# 07_MIMXRT1170_PART3.net
KiCad netlist of a schematic drawn in Altium Designer
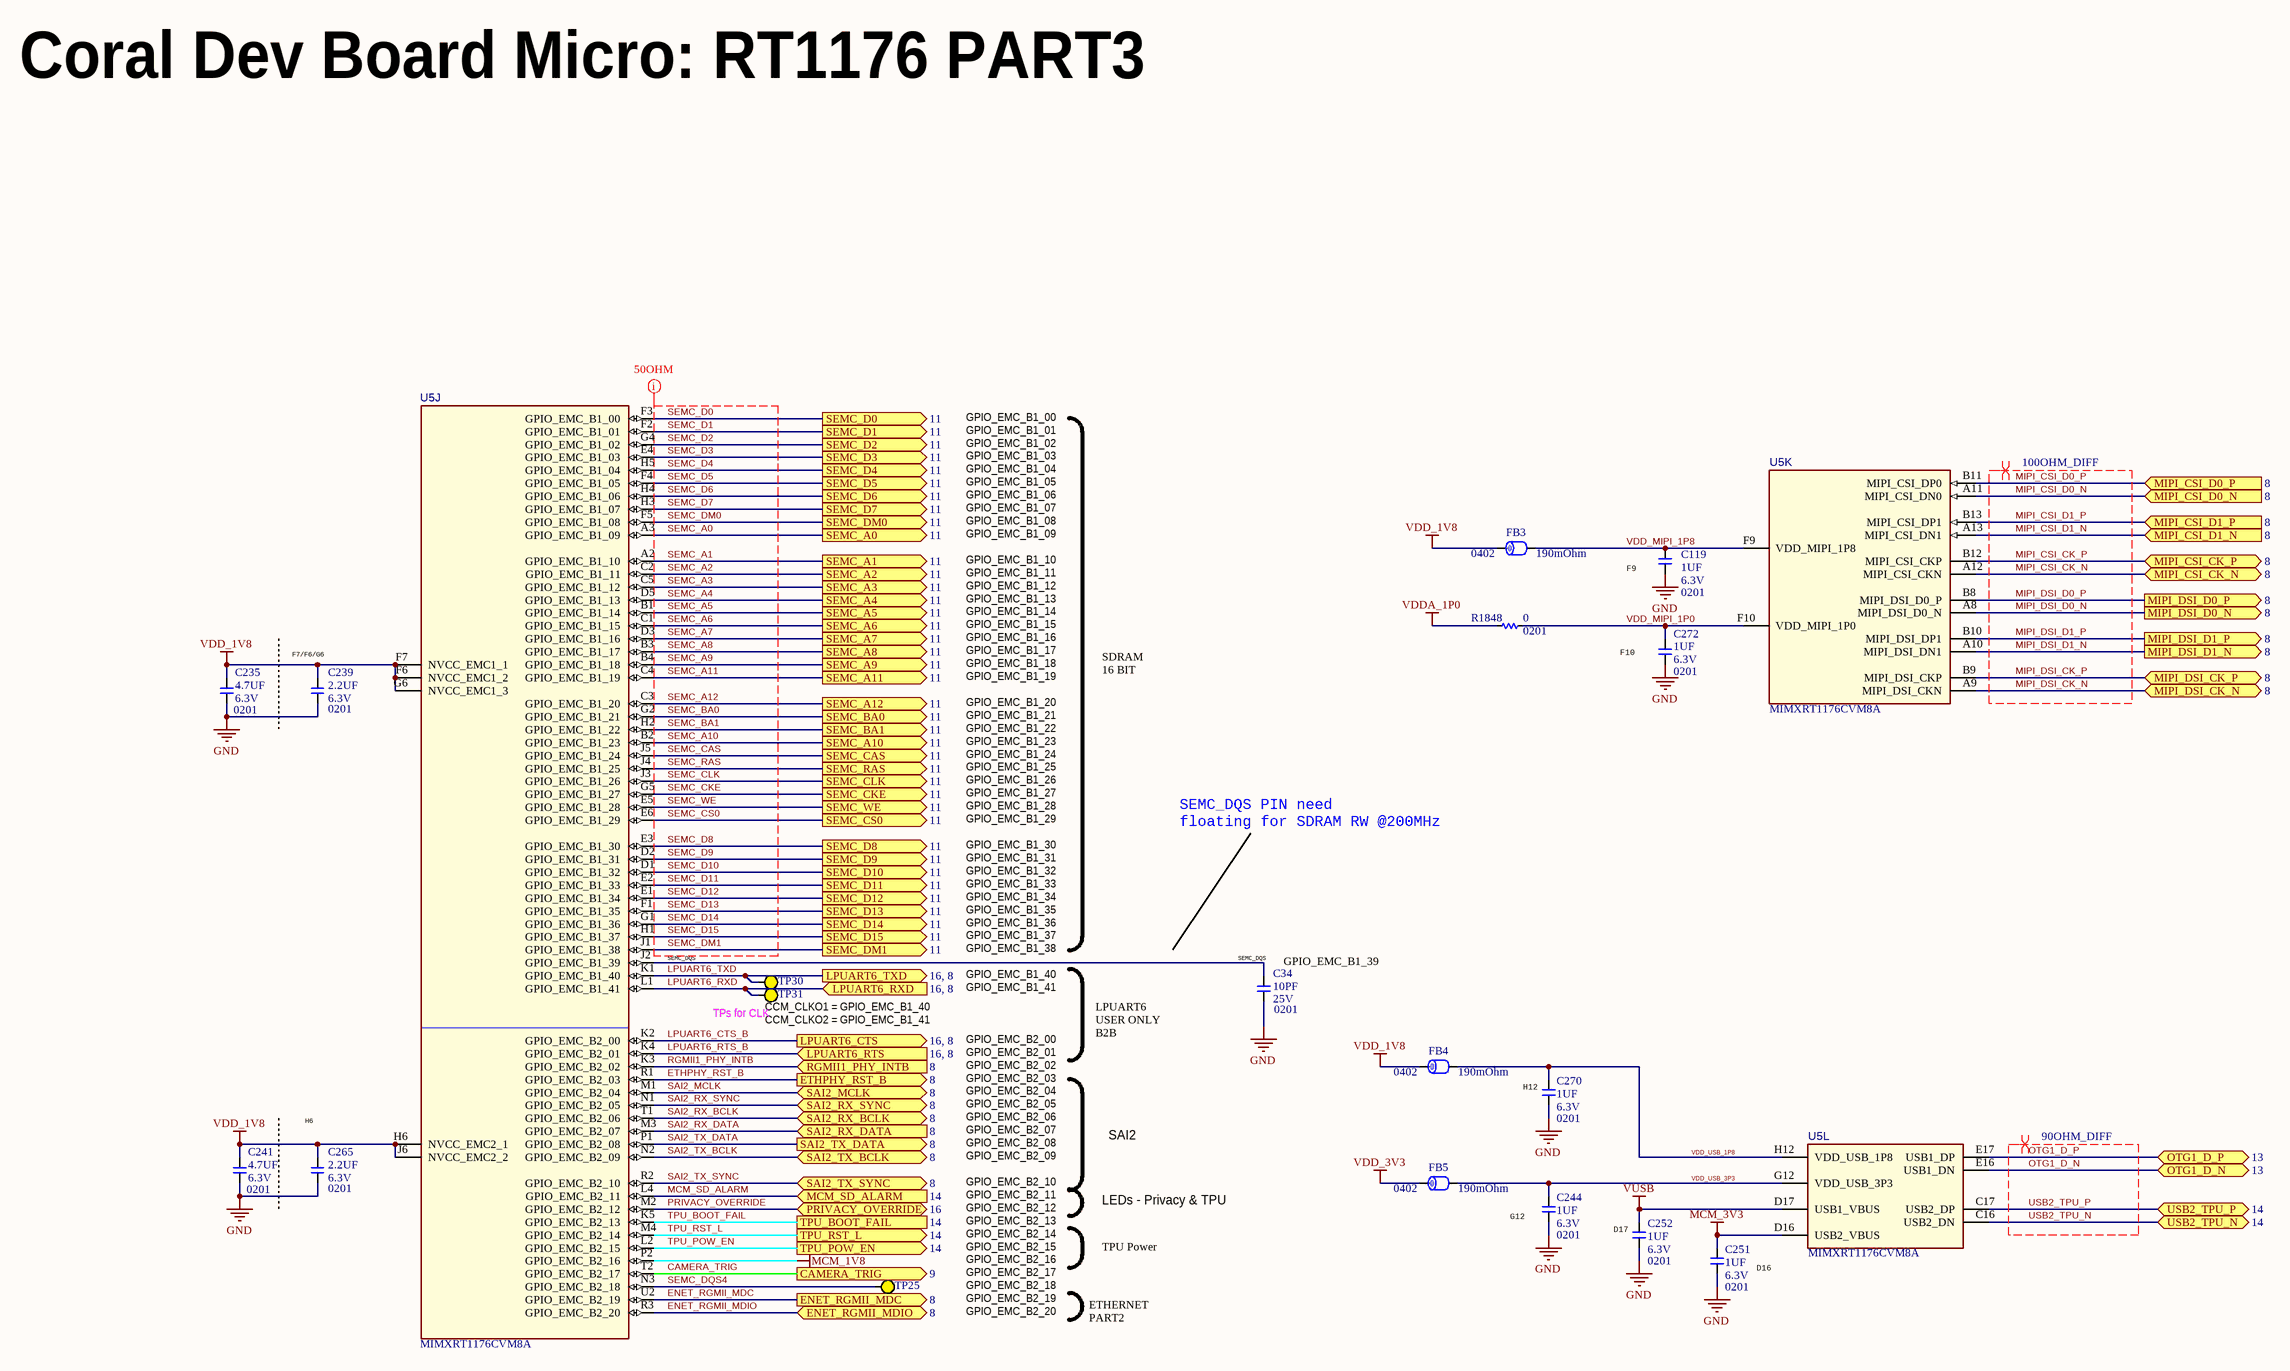
[diagram p0: 07 MIMXRT1170 PART3.SchDoc]

(export (version "E")
  (design (tool "Eeschema 10.0.6"))
  (components
    (comp (ref "C34")
      (value "10PF")
      (footprint "C0201Y")
      (description "CAP, CER, NP0, 10pF, 25V, 5%, 0201, 0.33mm T")
      (fields
        (field (name "MFG") "MURATA")
        (field (name "PACKAGE") "0201")
        (field (name "VOLTAGE") "25V")
        (field (name "TOLERANCE") "5%")
      )
      (libsource (lib "AltiumReleaseLibDB") (part "__Template_Cap"))
    )
    (comp (ref "C119")
      (value "1UF")
      (footprint "C0201_H0.39MM")
      (description "CAP, CER, X6S, 1uF, 20%, 6.3V, 0201, 0.39mm")
      (fields
        (field (name "MFG") "MURATA")
        (field (name "PACKAGE") "0201")
        (field (name "VOLTAGE") "6.3V")
        (field (name "TOLERANCE") "20%")
      )
      (libsource (lib "AltiumReleaseLibDB") (part "__Template_Cap"))
    )
    (comp (ref "C235")
      (value "4.7UF")
      (footprint "C0201Y")
      (description "CAP, CER, X5R, 4.7uF, 20%, 6.3V, 0201")
      (fields
        (field (name "MFG") "MURATA")
        (field (name "PACKAGE") "0201")
        (field (name "VOLTAGE") "6.3V")
        (field (name "TOLERANCE") "20%")
      )
      (libsource (lib "AltiumReleaseLibDB") (part "__Template_Cap"))
    )
    (comp (ref "C239")
      (value "2.2UF")
      (footprint "C0201_H0.39MM")
      (description "CAP, CER, X5R, 2.2uF, 20%, 6.3V, 0201, 0.39mm")
      (fields
        (field (name "MFG") "YAGEO")
        (field (name "PACKAGE") "0201")
        (field (name "VOLTAGE") "6.3V")
        (field (name "TOLERANCE") "20%")
      )
      (libsource (lib "AltiumReleaseLibDB") (part "__Template_Cap"))
    )
    (comp (ref "C241")
      (value "4.7UF")
      (footprint "C0201Y")
      (description "CAP, CER, X5R, 4.7uF, 20%, 6.3V, 0201")
      (fields
        (field (name "MFG") "MURATA")
        (field (name "PACKAGE") "0201")
        (field (name "VOLTAGE") "6.3V")
        (field (name "TOLERANCE") "20%")
      )
      (libsource (lib "AltiumReleaseLibDB") (part "__Template_Cap"))
    )
    (comp (ref "C244")
      (value "1UF")
      (footprint "C0201_H0.39MM")
      (description "CAP, CER, X6S, 1uF, 20%, 6.3V, 0201, 0.39mm")
      (fields
        (field (name "MFG") "MURATA")
        (field (name "PACKAGE") "0201")
        (field (name "VOLTAGE") "6.3V")
        (field (name "TOLERANCE") "20%")
      )
      (libsource (lib "AltiumReleaseLibDB") (part "__Template_Cap"))
    )
    (comp (ref "C251")
      (value "1UF")
      (footprint "C0201_H0.39MM")
      (description "CAP, CER, X6S, 1uF, 20%, 6.3V, 0201, 0.39mm")
      (fields
        (field (name "MFG") "MURATA")
        (field (name "PACKAGE") "0201")
        (field (name "VOLTAGE") "6.3V")
        (field (name "TOLERANCE") "20%")
      )
      (libsource (lib "AltiumReleaseLibDB") (part "__Template_Cap"))
    )
    (comp (ref "C252")
      (value "1UF")
      (footprint "C0201_H0.39MM")
      (description "CAP, CER, X6S, 1uF, 20%, 6.3V, 0201, 0.39mm")
      (fields
        (field (name "MFG") "MURATA")
        (field (name "PACKAGE") "0201")
        (field (name "VOLTAGE") "6.3V")
        (field (name "TOLERANCE") "20%")
      )
      (libsource (lib "AltiumReleaseLibDB") (part "__Template_Cap"))
    )
    (comp (ref "C265")
      (value "2.2UF")
      (footprint "C0201_H0.39MM")
      (description "CAP, CER, X5R, 2.2uF, 20%, 6.3V, 0201, 0.39mm")
      (fields
        (field (name "MFG") "YAGEO")
        (field (name "PACKAGE") "0201")
        (field (name "VOLTAGE") "6.3V")
        (field (name "TOLERANCE") "20%")
      )
      (libsource (lib "AltiumReleaseLibDB") (part "__Template_Cap"))
    )
    (comp (ref "C270")
      (value "1UF")
      (footprint "C0201_H0.39MM")
      (description "CAP, CER, X6S, 1uF, 20%, 6.3V, 0201, 0.39mm")
      (fields
        (field (name "MFG") "MURATA")
        (field (name "PACKAGE") "0201")
        (field (name "VOLTAGE") "6.3V")
        (field (name "TOLERANCE") "20%")
      )
      (libsource (lib "AltiumReleaseLibDB") (part "__Template_Cap"))
    )
    (comp (ref "C272")
      (value "1UF")
      (footprint "C0201_H0.39MM")
      (description "CAP, CER, X6S, 1uF, 20%, 6.3V, 0201, 0.39mm")
      (fields
        (field (name "MFG") "MURATA")
        (field (name "PACKAGE") "0201")
        (field (name "VOLTAGE") "6.3V")
        (field (name "TOLERANCE") "20%")
      )
      (libsource (lib "AltiumReleaseLibDB") (part "__Template_Cap"))
    )
    (comp (ref "FB3")
      (value "__Template_Ferrite_Bead")
      (footprint "L0402_H0.55MM")
      (description "FERRITE, BEAD, 120 OHMS@100MHZ, 25%, 550mA, 190 mOHM DCR, 0402")
      (fields
        (field (name "MFG") "Murata Electronics")
        (field (name "PACKAGE") "0402")
        (field (name "RDC MAX") "190mOhm")
      )
      (libsource (lib "AltiumReleaseLibDB") (part "__Template_Ferrite_Bead"))
    )
    (comp (ref "FB4")
      (value "__Template_Ferrite_Bead")
      (footprint "L0402_H0.55MM")
      (description "FERRITE, BEAD, 120 OHMS@100MHZ, 25%, 550mA, 190 mOHM DCR, 0402")
      (fields
        (field (name "MFG") "Murata Electronics")
        (field (name "PACKAGE") "0402")
        (field (name "RDC MAX") "190mOhm")
      )
      (libsource (lib "AltiumReleaseLibDB") (part "__Template_Ferrite_Bead"))
    )
    (comp (ref "FB5")
      (value "__Template_Ferrite_Bead")
      (footprint "L0402_H0.55MM")
      (description "FERRITE, BEAD, 120 OHMS@100MHZ, 25%, 550mA, 190 mOHM DCR, 0402")
      (fields
        (field (name "MFG") "Murata Electronics")
        (field (name "PACKAGE") "0402")
        (field (name "RDC MAX") "190mOhm")
      )
      (libsource (lib "AltiumReleaseLibDB") (part "__Template_Ferrite_Bead"))
    )
    (comp (ref "R1848")
      (value "0")
      (footprint "R0201")
      (description "RES, 0.0, 1/20W, 0201")
      (fields (field (name "MFG") "PANASONIC") (field (name "PACKAGE") "0201") (field (name "POWER") "1/20W"))
      (libsource (lib "AltiumReleaseLibDB") (part "__Template_Resistor"))
    )
    (comp (ref "TP25")
      (value "TESTPAD_30MIL")
      (footprint "TESTPAD_SMT_30MIL")
      (description "TESTPAD_SMT_30MIL")
      (fields (field (name "MFG") "_PCB Feature"))
      (libsource (lib "AltiumReleaseLibDB") (part "TESTPAD_30MIL"))
    )
    (comp (ref "TP30")
      (value "TESTPAD_30MIL")
      (footprint "TESTPAD_SMT_30MIL")
      (description "TESTPAD_SMT_30MIL")
      (fields (field (name "MFG") "_PCB Feature"))
      (libsource (lib "AltiumReleaseLibDB") (part "TESTPAD_30MIL"))
    )
    (comp (ref "TP31")
      (value "TESTPAD_30MIL")
      (footprint "TESTPAD_SMT_30MIL")
      (description "TESTPAD_SMT_30MIL")
      (fields (field (name "MFG") "_PCB Feature"))
      (libsource (lib "AltiumReleaseLibDB") (part "TESTPAD_30MIL"))
    )
    (comp (ref "U5")
      (value "MCU_MIMXRT1176CVM8A")
      (footprint "BGA289C80P17X17_1400X14000X152")
      (description "IC, PROCESSOR, MIMXRT1176CV, ARM CORTEX-M4/M7, 2MB RAM, SDRAM, WLAN, BGA-289")
      (fields (field (name "MFG") "NXP Semiconductors") (field (name "MFG P/N") "MIMXRT1176CVM8A"))
      (libsource (lib "AltiumReleaseLibDB") (part "MCU_MIMXRT1176CVM8A"))
    )
  )
  (nets
    (net (code "1") (name "/CAMERA_TRIG") (class "Default")
      (node (ref "U5") (pin "T2") (pinfunction "GPIO_EMC_B2_17_T2") (pintype "bidirectional"))
    )
    (net (code "2") (name "/ENET_RGMII_MDC") (class "Default")
      (node (ref "U5") (pin "U2") (pinfunction "GPIO_EMC_B2_19_U2") (pintype "bidirectional"))
    )
    (net (code "3") (name "/ENET_RGMII_MDIO") (class "Default")
      (node (ref "U5") (pin "R3") (pinfunction "GPIO_EMC_B2_20_R3") (pintype "bidirectional"))
    )
    (net (code "4") (name "/ETHPHY_RST_B") (class "Default")
      (node (ref "U5") (pin "R1") (pinfunction "GPIO_EMC_B2_03_R1") (pintype "bidirectional"))
    )
    (net (code "5") (name "/LPUART6_CTS_B") (class "Default")
      (node (ref "U5") (pin "K2") (pinfunction "GPIO_EMC_B2_00_K2") (pintype "bidirectional"))
    )
    (net (code "6") (name "/LPUART6_RTS_B") (class "Default")
      (node (ref "U5") (pin "K4") (pinfunction "GPIO_EMC_B2_01_K4") (pintype "bidirectional"))
    )
    (net (code "7") (name "/LPUART6_RXD") (class "Default")
      (node (ref "TP31") (pin "1") (pintype "passive"))
      (node (ref "U5") (pin "L1") (pinfunction "GPIO_EMC_B1_41_L1") (pintype "bidirectional"))
    )
    (net (code "8") (name "/LPUART6_TXD") (class "Default")
      (node (ref "TP30") (pin "1") (pintype "passive"))
      (node (ref "U5") (pin "K1") (pinfunction "GPIO_EMC_B1_40_K1") (pintype "bidirectional"))
    )
    (net (code "9") (name "/MCM_SD_ALARM") (class "Default")
      (node (ref "U5") (pin "L4") (pinfunction "GPIO_EMC_B2_11_L4") (pintype "bidirectional"))
    )
    (net (code "10") (name "/MIPI_CSI_CK_N") (class "Default")
      (node (ref "U5") (pin "A12") (pinfunction "MIPI_CSI_CKN_A12") (pintype "passive"))
    )
    (net (code "11") (name "/MIPI_CSI_CK_P") (class "Default")
      (node (ref "U5") (pin "B12") (pinfunction "MIPI_CSI_CKP_B12") (pintype "passive"))
    )
    (net (code "12") (name "/MIPI_CSI_D0_N") (class "Default")
      (node (ref "U5") (pin "A11") (pinfunction "MIPI_CSI_DN0_A11") (pintype "input"))
    )
    (net (code "13") (name "/MIPI_CSI_D0_P") (class "Default")
      (node (ref "U5") (pin "B11") (pinfunction "MIPI_CSI_DP0_B11") (pintype "input"))
    )
    (net (code "14") (name "/MIPI_CSI_D1_N") (class "Default")
      (node (ref "U5") (pin "A13") (pinfunction "MIPI_CSI_DN1_A13") (pintype "input"))
    )
    (net (code "15") (name "/MIPI_CSI_D1_P") (class "Default")
      (node (ref "U5") (pin "B13") (pinfunction "MIPI_CSI_DP1_B13") (pintype "input"))
    )
    (net (code "16") (name "/MIPI_DSI_CK_N") (class "Default")
      (node (ref "U5") (pin "A9") (pinfunction "MIPI_DSI_CKN_A9") (pintype "passive"))
    )
    (net (code "17") (name "/MIPI_DSI_CK_P") (class "Default")
      (node (ref "U5") (pin "B9") (pinfunction "MIPI_DSI_CKP_B9") (pintype "passive"))
    )
    (net (code "18") (name "/MIPI_DSI_D0_N") (class "Default")
      (node (ref "U5") (pin "A8") (pinfunction "MIPI_DSI_DN0_A8") (pintype "passive"))
    )
    (net (code "19") (name "/MIPI_DSI_D0_P") (class "Default")
      (node (ref "U5") (pin "B8") (pinfunction "MIPI_DSI_DP0_B8") (pintype "passive"))
    )
    (net (code "20") (name "/MIPI_DSI_D1_N") (class "Default")
      (node (ref "U5") (pin "A10") (pinfunction "MIPI_DSI_DN1_A10") (pintype "passive"))
    )
    (net (code "21") (name "/MIPI_DSI_D1_P") (class "Default")
      (node (ref "U5") (pin "B10") (pinfunction "MIPI_DSI_DP1_B10") (pintype "passive"))
    )
    (net (code "22") (name "/OTG1_D_N") (class "Default")
      (node (ref "U5") (pin "E16") (pinfunction "USB1_DN_E16") (pintype "passive"))
    )
    (net (code "23") (name "/OTG1_D_P") (class "Default")
      (node (ref "U5") (pin "E17") (pinfunction "USB1_DP_E17") (pintype "passive"))
    )
    (net (code "24") (name "/PRIVACY_OVERRIDE") (class "Default")
      (node (ref "U5") (pin "M2") (pinfunction "GPIO_EMC_B2_12_M2") (pintype "bidirectional"))
    )
    (net (code "25") (name "/RGMII1_PHY_INTB") (class "Default")
      (node (ref "U5") (pin "K3") (pinfunction "GPIO_EMC_B2_02_K3") (pintype "bidirectional"))
    )
    (net (code "26") (name "/SAI2_MCLK") (class "Default")
      (node (ref "U5") (pin "M1") (pinfunction "GPIO_EMC_B2_04_M1") (pintype "bidirectional"))
    )
    (net (code "27") (name "/SAI2_RX_BCLK") (class "Default")
      (node (ref "U5") (pin "T1") (pinfunction "GPIO_EMC_B2_06_T1") (pintype "bidirectional"))
    )
    (net (code "28") (name "/SAI2_RX_DATA") (class "Default")
      (node (ref "U5") (pin "M3") (pinfunction "GPIO_EMC_B2_07_M3") (pintype "bidirectional"))
    )
    (net (code "29") (name "/SAI2_RX_SYNC") (class "Default")
      (node (ref "U5") (pin "N1") (pinfunction "GPIO_EMC_B2_05_N1") (pintype "bidirectional"))
    )
    (net (code "30") (name "/SAI2_TX_BCLK") (class "Default")
      (node (ref "U5") (pin "N2") (pinfunction "GPIO_EMC_B2_09_N2") (pintype "bidirectional"))
    )
    (net (code "31") (name "/SAI2_TX_DATA") (class "Default")
      (node (ref "U5") (pin "P1") (pinfunction "GPIO_EMC_B2_08_P1") (pintype "bidirectional"))
    )
    (net (code "32") (name "/SAI2_TX_SYNC") (class "Default")
      (node (ref "U5") (pin "R2") (pinfunction "GPIO_EMC_B2_10_R2") (pintype "bidirectional"))
    )
    (net (code "33") (name "/SEMC_A0") (class "Default")
      (node (ref "U5") (pin "A3") (pinfunction "GPIO_EMC_B1_09_A3") (pintype "bidirectional"))
    )
    (net (code "34") (name "/SEMC_A1") (class "Default")
      (node (ref "U5") (pin "A2") (pinfunction "GPIO_EMC_B1_10_A2") (pintype "bidirectional"))
    )
    (net (code "35") (name "/SEMC_A2") (class "Default")
      (node (ref "U5") (pin "C2") (pinfunction "GPIO_EMC_B1_11_C2") (pintype "bidirectional"))
    )
    (net (code "36") (name "/SEMC_A3") (class "Default")
      (node (ref "U5") (pin "C5") (pinfunction "GPIO_EMC_B1_12_C5") (pintype "bidirectional"))
    )
    (net (code "37") (name "/SEMC_A4") (class "Default")
      (node (ref "U5") (pin "D5") (pinfunction "GPIO_EMC_B1_13_D5") (pintype "bidirectional"))
    )
    (net (code "38") (name "/SEMC_A5") (class "Default")
      (node (ref "U5") (pin "B1") (pinfunction "GPIO_EMC_B1_14_B1") (pintype "bidirectional"))
    )
    (net (code "39") (name "/SEMC_A6") (class "Default")
      (node (ref "U5") (pin "C1") (pinfunction "GPIO_EMC_B1_15_C1") (pintype "bidirectional"))
    )
    (net (code "40") (name "/SEMC_A7") (class "Default")
      (node (ref "U5") (pin "D3") (pinfunction "GPIO_EMC_B1_16_D3") (pintype "bidirectional"))
    )
    (net (code "41") (name "/SEMC_A8") (class "Default")
      (node (ref "U5") (pin "B3") (pinfunction "GPIO_EMC_B1_17_B3") (pintype "bidirectional"))
    )
    (net (code "42") (name "/SEMC_A9") (class "Default")
      (node (ref "U5") (pin "B4") (pinfunction "GPIO_EMC_B1_18_B4") (pintype "bidirectional"))
    )
    (net (code "43") (name "/SEMC_A10") (class "Default")
      (node (ref "U5") (pin "B2") (pinfunction "GPIO_EMC_B1_23_B2") (pintype "bidirectional"))
    )
    (net (code "44") (name "/SEMC_A11") (class "Default")
      (node (ref "U5") (pin "C4") (pinfunction "GPIO_EMC_B1_19_C4") (pintype "bidirectional"))
    )
    (net (code "45") (name "/SEMC_A12") (class "Default")
      (node (ref "U5") (pin "C3") (pinfunction "GPIO_EMC_B1_20_C3") (pintype "bidirectional"))
    )
    (net (code "46") (name "/SEMC_BA0") (class "Default")
      (node (ref "U5") (pin "G2") (pinfunction "GPIO_EMC_B1_21_G2") (pintype "bidirectional"))
    )
    (net (code "47") (name "/SEMC_BA1") (class "Default")
      (node (ref "U5") (pin "H2") (pinfunction "GPIO_EMC_B1_22_H2") (pintype "bidirectional"))
    )
    (net (code "48") (name "/SEMC_CAS") (class "Default")
      (node (ref "U5") (pin "J5") (pinfunction "GPIO_EMC_B1_24_J5") (pintype "bidirectional"))
    )
    (net (code "49") (name "/SEMC_CKE") (class "Default")
      (node (ref "U5") (pin "G5") (pinfunction "GPIO_EMC_B1_27_G5") (pintype "bidirectional"))
    )
    (net (code "50") (name "/SEMC_CLK") (class "Default")
      (node (ref "U5") (pin "J3") (pinfunction "GPIO_EMC_B1_26_J3") (pintype "bidirectional"))
    )
    (net (code "51") (name "/SEMC_CS0") (class "Default")
      (node (ref "U5") (pin "E6") (pinfunction "GPIO_EMC_B1_29_E6") (pintype "bidirectional"))
    )
    (net (code "52") (name "/SEMC_D0") (class "Default")
      (node (ref "U5") (pin "F3") (pinfunction "GPIO_EMC_B1_00_F3") (pintype "bidirectional"))
    )
    (net (code "53") (name "/SEMC_D1") (class "Default")
      (node (ref "U5") (pin "F2") (pinfunction "GPIO_EMC_B1_01_F2") (pintype "bidirectional"))
    )
    (net (code "54") (name "/SEMC_D2") (class "Default")
      (node (ref "U5") (pin "G4") (pinfunction "GPIO_EMC_B1_02_G4") (pintype "bidirectional"))
    )
    (net (code "55") (name "/SEMC_D3") (class "Default")
      (node (ref "U5") (pin "E4") (pinfunction "GPIO_EMC_B1_03_E4") (pintype "bidirectional"))
    )
    (net (code "56") (name "/SEMC_D4") (class "Default")
      (node (ref "U5") (pin "H5") (pinfunction "GPIO_EMC_B1_04_H5") (pintype "bidirectional"))
    )
    (net (code "57") (name "/SEMC_D5") (class "Default")
      (node (ref "U5") (pin "F4") (pinfunction "GPIO_EMC_B1_05_F4") (pintype "bidirectional"))
    )
    (net (code "58") (name "/SEMC_D6") (class "Default")
      (node (ref "U5") (pin "H4") (pinfunction "GPIO_EMC_B1_06_H4") (pintype "bidirectional"))
    )
    (net (code "59") (name "/SEMC_D7") (class "Default")
      (node (ref "U5") (pin "H3") (pinfunction "GPIO_EMC_B1_07_H3") (pintype "bidirectional"))
    )
    (net (code "60") (name "/SEMC_D8") (class "Default")
      (node (ref "U5") (pin "E3") (pinfunction "GPIO_EMC_B1_30_E3") (pintype "bidirectional"))
    )
    (net (code "61") (name "/SEMC_D9") (class "Default")
      (node (ref "U5") (pin "D2") (pinfunction "GPIO_EMC_B1_31_D2") (pintype "bidirectional"))
    )
    (net (code "62") (name "/SEMC_D10") (class "Default")
      (node (ref "U5") (pin "D1") (pinfunction "GPIO_EMC_B1_32_D1") (pintype "bidirectional"))
    )
    (net (code "63") (name "/SEMC_D11") (class "Default")
      (node (ref "U5") (pin "E2") (pinfunction "GPIO_EMC_B1_33_E2") (pintype "bidirectional"))
    )
    (net (code "64") (name "/SEMC_D12") (class "Default")
      (node (ref "U5") (pin "E1") (pinfunction "GPIO_EMC_B1_34_E1") (pintype "bidirectional"))
    )
    (net (code "65") (name "/SEMC_D13") (class "Default")
      (node (ref "U5") (pin "F1") (pinfunction "GPIO_EMC_B1_35_F1") (pintype "bidirectional"))
    )
    (net (code "66") (name "/SEMC_D14") (class "Default")
      (node (ref "U5") (pin "G1") (pinfunction "GPIO_EMC_B1_36_G1") (pintype "bidirectional"))
    )
    (net (code "67") (name "/SEMC_D15") (class "Default")
      (node (ref "U5") (pin "H1") (pinfunction "GPIO_EMC_B1_37_H1") (pintype "bidirectional"))
    )
    (net (code "68") (name "/SEMC_DM0") (class "Default")
      (node (ref "U5") (pin "F5") (pinfunction "GPIO_EMC_B1_08_F5") (pintype "bidirectional"))
    )
    (net (code "69") (name "/SEMC_DM1") (class "Default")
      (node (ref "U5") (pin "J1") (pinfunction "GPIO_EMC_B1_38_J1") (pintype "bidirectional"))
    )
    (net (code "70") (name "/SEMC_DQS4") (class "Default")
      (node (ref "TP25") (pin "1") (pintype "passive"))
      (node (ref "U5") (pin "N3") (pinfunction "GPIO_EMC_B2_18_N3") (pintype "bidirectional"))
    )
    (net (code "71") (name "/SEMC_RAS") (class "Default")
      (node (ref "U5") (pin "J4") (pinfunction "GPIO_EMC_B1_25_J4") (pintype "bidirectional"))
    )
    (net (code "72") (name "/SEMC_WE") (class "Default")
      (node (ref "U5") (pin "E5") (pinfunction "GPIO_EMC_B1_28_E5") (pintype "bidirectional"))
    )
    (net (code "73") (name "/TPU_BOOT_FAIL") (class "Default")
      (node (ref "U5") (pin "K5") (pinfunction "GPIO_EMC_B2_13_K5") (pintype "bidirectional"))
    )
    (net (code "74") (name "/TPU_POW_EN") (class "Default")
      (node (ref "U5") (pin "L2") (pinfunction "GPIO_EMC_B2_15_L2") (pintype "bidirectional"))
    )
    (net (code "75") (name "/TPU_RST_L") (class "Default")
      (node (ref "U5") (pin "M4") (pinfunction "GPIO_EMC_B2_14_M4") (pintype "bidirectional"))
    )
    (net (code "76") (name "/USB2_TPU_N") (class "Default")
      (node (ref "U5") (pin "C16") (pinfunction "USB2_DN_C16") (pintype "passive"))
    )
    (net (code "77") (name "/USB2_TPU_P") (class "Default")
      (node (ref "U5") (pin "C17") (pinfunction "USB2_DP_C17") (pintype "passive"))
    )
    (net (code "78") (name "/VDD_MIPI_1P0") (class "Default")
      (node (ref "C272") (pin "1") (pintype "passive"))
      (node (ref "R1848") (pin "2") (pintype "passive"))
      (node (ref "U5") (pin "F10") (pinfunction "VDD_MIPI_1P0_F10") (pintype "power_in"))
    )
    (net (code "79") (name "/VDD_MIPI_1P8") (class "Default")
      (node (ref "C119") (pin "1") (pintype "passive"))
      (node (ref "FB3") (pin "2") (pinfunction "2_2") (pintype "passive"))
      (node (ref "U5") (pin "F9") (pinfunction "VDD_MIPI_1P8_F9") (pintype "power_in"))
    )
    (net (code "80") (name "/VDD_USB_1P8") (class "Default")
      (node (ref "C270") (pin "1") (pintype "passive"))
      (node (ref "FB4") (pin "2") (pinfunction "2_2") (pintype "passive"))
      (node (ref "U5") (pin "H12") (pinfunction "VDD_USB_1P8_H12") (pintype "power_in"))
    )
    (net (code "81") (name "/VDD_USB_3P3") (class "Default")
      (node (ref "C244") (pin "1") (pintype "passive"))
      (node (ref "FB5") (pin "2") (pinfunction "2_2") (pintype "passive"))
      (node (ref "U5") (pin "G12") (pinfunction "VDD_USB_3P3_G12") (pintype "power_in"))
    )
    (net (code "82") (name "GND") (class "Default")
      (node (ref "C119") (pin "2") (pintype "passive"))
      (node (ref "C235") (pin "2") (pintype "passive"))
      (node (ref "C239") (pin "2") (pintype "passive"))
      (node (ref "C241") (pin "2") (pintype "passive"))
      (node (ref "C244") (pin "2") (pintype "passive"))
      (node (ref "C251") (pin "2") (pintype "passive"))
      (node (ref "C252") (pin "2") (pintype "passive"))
      (node (ref "C265") (pin "2") (pintype "passive"))
      (node (ref "C270") (pin "2") (pintype "passive"))
      (node (ref "C272") (pin "2") (pintype "passive"))
      (node (ref "C34") (pin "2") (pintype "passive"))
    )
    (net (code "83") (name "MCM_1V8") (class "Default")
      (node (ref "U5") (pin "P2") (pinfunction "GPIO_EMC_B2_16_P2") (pintype "bidirectional"))
    )
    (net (code "84") (name "MCM_3V3") (class "Default")
      (node (ref "C251") (pin "1") (pintype "passive"))
      (node (ref "U5") (pin "D16") (pinfunction "USB2_VBUS_D16") (pintype "passive"))
    )
    (net (code "85") (name "Net-(U5J-GPIO_EMC_B1_39)") (class "Default")
      (node (ref "C34") (pin "1") (pintype "passive"))
      (node (ref "U5") (pin "J2") (pinfunction "GPIO_EMC_B1_39_J2") (pintype "bidirectional"))
    )
    (net (code "86") (name "VDDA_1P0") (class "Default") (node (ref "R1848") (pin "1") (pintype "passive")))
    (net (code "87") (name "VDD_1V8") (class "Default")
      (node (ref "C235") (pin "1") (pintype "passive"))
      (node (ref "C239") (pin "1") (pintype "passive"))
      (node (ref "C241") (pin "1") (pintype "passive"))
      (node (ref "C265") (pin "1") (pintype "passive"))
      (node (ref "FB3") (pin "1") (pinfunction "1_1") (pintype "passive"))
      (node (ref "FB4") (pin "1") (pinfunction "1_1") (pintype "passive"))
      (node (ref "U5") (pin "F6") (pinfunction "NVCC_EMC1_2_F6") (pintype "power_in"))
      (node (ref "U5") (pin "F7") (pinfunction "NVCC_EMC1_1_F7") (pintype "power_in"))
      (node (ref "U5") (pin "G6") (pinfunction "NVCC_EMC1_3_G6") (pintype "power_in"))
      (node (ref "U5") (pin "H6") (pinfunction "NVCC_EMC2_1_H6") (pintype "power_in"))
      (node (ref "U5") (pin "J6") (pinfunction "NVCC_EMC2_2_J6") (pintype "power_in"))
    )
    (net (code "88") (name "VDD_3V3") (class "Default")
      (node (ref "FB5") (pin "1") (pinfunction "1_1") (pintype "passive"))
    )
    (net (code "89") (name "VUSB") (class "Default")
      (node (ref "C252") (pin "1") (pintype "passive"))
      (node (ref "U5") (pin "D17") (pinfunction "USB1_VBUS_D17") (pintype "passive"))
    )
  )
)
